# CH32V005F6U6.net
KiCad netlist of a schematic drawn in Altium Designer
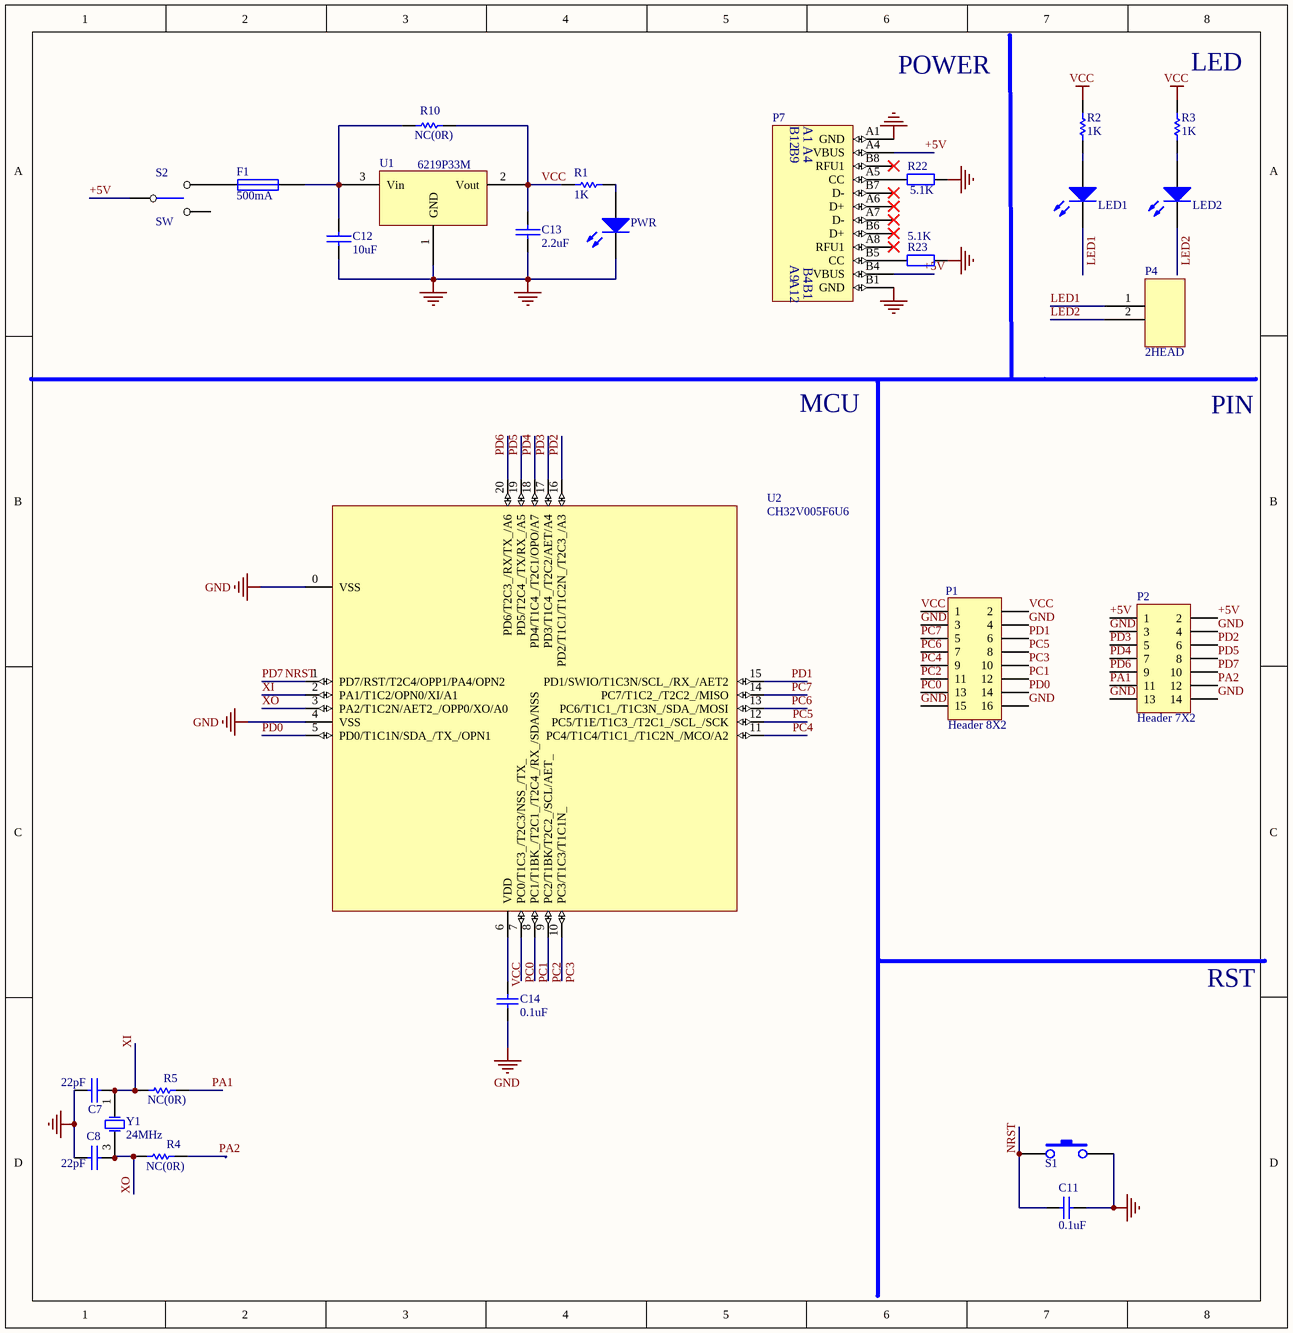
[diagram p0: CH32V005F6U6.SchDoc]

(export (version "E")
  (design (tool "Eeschema 10.0.6"))
  (components
    (comp (ref "C7")
      (value "22pF")
      (footprint "0402_C")
      (description "Capacitor")
      (libsource (lib "*") (part "CAP"))
    )
    (comp (ref "C8")
      (value "22pF")
      (footprint "0402_C")
      (description "Capacitor")
      (libsource (lib "*") (part "CAP"))
    )
    (comp (ref "C11")
      (value "0.1uF")
      (footprint "0603_C")
      (description "Capacitor")
      (fields (field (name "PUBLISHER") "Altium Limited"))
      (libsource (lib "*") (part "Cap"))
    )
    (comp (ref "C12")
      (value "10uF")
      (footprint "0603_C")
      (description "Capacitor")
      (libsource (lib "wch_sch_others") (part "CAP"))
    )
    (comp (ref "C13")
      (value "2.2uF")
      (footprint "0402_C")
      (description "Capacitor")
      (libsource (lib "wch_sch_others") (part "CAP"))
    )
    (comp (ref "C14")
      (value "0.1uF")
      (footprint "0603_C")
      (description "Capacitor")
      (fields (field (name "PUBLISHER") "Altium Limited"))
      (libsource (lib "*") (part "Cap"))
    )
    (comp (ref "F1")
      (value "500mA")
      (footprint "0603")
      (description "Fuse")
      (libsource (lib "*") (part "FUSE1"))
    )
    (comp (ref "LED1")
      (value "LED1   blue")
      (footprint "0603+")
      (description "Typical INFRARED GaAs LED")
      (fields (field (name "PUBLISHER") "Altium Limited"))
      (libsource (lib "") (part "LED0_1"))
    )
    (comp (ref "LED2")
      (value "LED2  blue")
      (footprint "0603+")
      (description "Typical INFRARED GaAs LED")
      (fields (field (name "PUBLISHER") "Altium Limited"))
      (libsource (lib "") (part "LED0_1"))
    )
    (comp (ref "P1")
      (value "Header 8X2")
      (footprint "HDR2X8")
      (description "Header, 8-Pin, Dual row")
      (fields (field (name "PUBLISHER") "Altium Limited"))
      (libsource (lib "Miscellaneous Connectors") (part "Header 8X2"))
    )
    (comp (ref "P2")
      (value "Header 7X2")
      (footprint "HDR2X7")
      (description "Header, 7-Pin, Dual row")
      (fields (field (name "PUBLISHER") "Altium Limited"))
      (libsource (lib "Miscellaneous Connectors") (part "Header 7X2"))
    )
    (comp (ref "P4") (value "2HEAD") (footprint "SIP2-2.54mm") (libsource (lib "*") (part "2HEAD")))
    (comp (ref "P7")
      (value "TYPE-C")
      (footprint "TYPE-C-Receptacle-2.0")
      (libsource (lib "*") (part "TYPE-C1"))
    )
    (comp (ref "PWR")
      (value "POWER  red")
      (footprint "0603+")
      (description "Typical INFRARED GaAs LED")
      (fields (field (name "PUBLISHER") "Altium Limited"))
      (libsource (lib "*") (part "LED0"))
    )
    (comp (ref "R1")
      (value "1K")
      (footprint "0402")
      (description "Semiconductor Resistor")
      (fields (field (name "PUBLISHER") "Altium Limited"))
      (libsource (lib "*") (part "Res Semi"))
    )
    (comp (ref "R2")
      (value "1K")
      (footprint "0402")
      (description "Semiconductor Resistor")
      (fields (field (name "PUBLISHER") "Altium Limited"))
      (libsource (lib "*") (part "Res Semi"))
    )
    (comp (ref "R3")
      (value "1K")
      (footprint "0402")
      (description "Semiconductor Resistor")
      (fields (field (name "PUBLISHER") "Altium Limited"))
      (libsource (lib "*") (part "Res Semi"))
    )
    (comp (ref "R4")
      (value "NC(0R)")
      (footprint "0402")
      (description "Semiconductor Resistor")
      (fields (field (name "Comment") "0R") (field (name "PUBLISHER") "Altium Limited"))
      (libsource (lib "*") (part "Res Semi"))
    )
    (comp (ref "R5")
      (value "NC(0R)")
      (footprint "0402")
      (description "Semiconductor Resistor")
      (fields (field (name "Comment") "0R") (field (name "PUBLISHER") "Altium Limited"))
      (libsource (lib "*") (part "Res Semi"))
    )
    (comp (ref "R10")
      (value "NC(0R)")
      (footprint "0402")
      (description "Semiconductor Resistor")
      (fields (field (name "Comment") "0R") (field (name "PUBLISHER") "Altium Limited"))
      (libsource (lib "*") (part "Res Semi"))
    )
    (comp (ref "R22")
      (value "5.1K")
      (footprint "0402")
      (description "Resistor")
      (libsource (lib "Miscellaneous Devices") (part "Res2"))
    )
    (comp (ref "R23")
      (value "5.1K")
      (footprint "0402")
      (description "Resistor")
      (libsource (lib "Miscellaneous Devices") (part "Res2"))
    )
    (comp (ref "S1") (value "NRST") (footprint "SMD_6.1x3.65x2.5mm-KEY") (libsource (lib "*") (part "KEY")))
    (comp (ref "S2") (value "SW") (footprint "SW1") (libsource (lib "*") (part "SW")))
    (comp (ref "U1")
      (value "6219P33M")
      (footprint "SOT-23")
      (libsource (lib "wch_sch_others") (part "6219P33M"))
    )
    (comp (ref "U2")
      (value "CH32V005F6U6")
      (footprint "QFN20_3X3")
      (description "RISC-V MCU, 48MHz, ADC/OPA/2*UART/I2C/SPI")
      (libsource (lib "DHXXXSCH") (part "CH32V005F6U6"))
    )
    (comp (ref "Y1")
      (value "24MHz")
      (footprint "XT3225")
      (description "Crystal Oscillator")
      (fields (field (name "PUBLISHER") "Altium Limited"))
      (libsource (lib "*") (part "XTAL"))
    )
  )
  (nets
    (net (code "1") (name "/+5V") (class "Default")
      (node (ref "P2") (pin "1") (pinfunction "1_1") (pintype "passive"))
      (node (ref "P2") (pin "2") (pinfunction "2_2") (pintype "passive"))
      (node (ref "P7") (pin "A4") (pinfunction "VBUS_A4") (pintype "bidirectional"))
      (node (ref "P7") (pin "B4") (pinfunction "VBUS_B4") (pintype "bidirectional"))
      (node (ref "S2") (pin "1") (pinfunction "1_1") (pintype "passive"))
    )
    (net (code "2") (name "/LED1") (class "Default")
      (node (ref "LED1") (pin "2") (pinfunction "K_2") (pintype "passive"))
      (node (ref "P4") (pin "1") (pintype "passive"))
    )
    (net (code "3") (name "/LED2") (class "Default")
      (node (ref "LED2") (pin "2") (pinfunction "K_2") (pintype "passive"))
      (node (ref "P4") (pin "2") (pintype "passive"))
    )
    (net (code "4") (name "/NRST") (class "Default")
      (node (ref "C11") (pin "2") (pinfunction "2_2") (pintype "passive"))
      (node (ref "P2") (pin "10") (pinfunction "10_10") (pintype "passive"))
      (node (ref "S1") (pin "1") (pinfunction "1_1") (pintype "passive"))
      (node (ref "U2") (pin "1") (pinfunction "PD7/RST/T2C4/OPP1/PA4/OPN2_1") (pintype "bidirectional"))
    )
    (net (code "5") (name "/PA1") (class "Default")
      (node (ref "P2") (pin "11") (pinfunction "11_11") (pintype "passive"))
      (node (ref "R5") (pin "2") (pinfunction "2_2") (pintype "passive"))
    )
    (net (code "6") (name "/PA2") (class "Default")
      (node (ref "P2") (pin "12") (pinfunction "12_12") (pintype "passive"))
      (node (ref "R4") (pin "2") (pinfunction "2_2") (pintype "passive"))
    )
    (net (code "7") (name "/PC0") (class "Default")
      (node (ref "P1") (pin "13") (pinfunction "13_13") (pintype "passive"))
      (node (ref "U2") (pin "7") (pinfunction "PC0/T1C3_/T2C3/NSS_/TX__7") (pintype "bidirectional"))
    )
    (net (code "8") (name "/PC1") (class "Default")
      (node (ref "P1") (pin "12") (pinfunction "12_12") (pintype "passive"))
      (node (ref "U2") (pin "8") (pinfunction "PC1/T1BK_/T2C1_/T2C4_/RX_/SDA/NSS_8") (pintype "bidirectional"))
    )
    (net (code "9") (name "/PC2") (class "Default")
      (node (ref "P1") (pin "11") (pinfunction "11_11") (pintype "passive"))
      (node (ref "U2") (pin "9") (pinfunction "PC2/T1BK/T2C2_/SCL/AET__9") (pintype "bidirectional"))
    )
    (net (code "10") (name "/PC3") (class "Default")
      (node (ref "P1") (pin "10") (pinfunction "10_10") (pintype "passive"))
      (node (ref "U2") (pin "10") (pinfunction "PC3/T1C3/T1C1N__10") (pintype "bidirectional"))
    )
    (net (code "11") (name "/PC4") (class "Default")
      (node (ref "P1") (pin "9") (pinfunction "9_9") (pintype "passive"))
      (node (ref "U2") (pin "11") (pinfunction "PC4/T1C4/T1C1_/T1C2N_/MCO/A2_11") (pintype "bidirectional"))
    )
    (net (code "12") (name "/PC5") (class "Default")
      (node (ref "P1") (pin "8") (pinfunction "8_8") (pintype "passive"))
      (node (ref "U2") (pin "12") (pinfunction "PC5/T1E/T1C3_/T2C1_/SCL_/SCK_12") (pintype "bidirectional"))
    )
    (net (code "13") (name "/PC6") (class "Default")
      (node (ref "P1") (pin "7") (pinfunction "7_7") (pintype "passive"))
      (node (ref "U2") (pin "13") (pinfunction "PC6/T1C1_/T1C3N_/SDA_/MOSI_13") (pintype "bidirectional"))
    )
    (net (code "14") (name "/PC7") (class "Default")
      (node (ref "P1") (pin "5") (pinfunction "5_5") (pintype "passive"))
      (node (ref "U2") (pin "14") (pinfunction "PC7/T1C2_/T2C2_/MISO_14") (pintype "bidirectional"))
    )
    (net (code "15") (name "/PD0") (class "Default")
      (node (ref "P1") (pin "14") (pinfunction "14_14") (pintype "passive"))
      (node (ref "U2") (pin "5") (pinfunction "PD0/T1C1N/SDA_/TX_/OPN1_5") (pintype "bidirectional"))
    )
    (net (code "16") (name "/PD1") (class "Default")
      (node (ref "P1") (pin "6") (pinfunction "6_6") (pintype "passive"))
      (node (ref "U2") (pin "15") (pinfunction "PD1/SWIO/T1C3N/SCL_/RX_/AET2_15") (pintype "bidirectional"))
    )
    (net (code "17") (name "/PD2") (class "Default")
      (node (ref "P2") (pin "6") (pinfunction "6_6") (pintype "passive"))
      (node (ref "U2") (pin "16") (pinfunction "PD2/T1C1/T1C2N_/T2C3_/A3_16") (pintype "bidirectional"))
    )
    (net (code "18") (name "/PD3") (class "Default")
      (node (ref "P2") (pin "5") (pinfunction "5_5") (pintype "passive"))
      (node (ref "U2") (pin "17") (pinfunction "PD3/T1C4_/T2C2/AET/A4_17") (pintype "bidirectional"))
    )
    (net (code "19") (name "/PD4") (class "Default")
      (node (ref "P2") (pin "7") (pinfunction "7_7") (pintype "passive"))
      (node (ref "U2") (pin "18") (pinfunction "PD4/T1C4_/T2C1/OPO/A7_18") (pintype "bidirectional"))
    )
    (net (code "20") (name "/PD5") (class "Default")
      (node (ref "P2") (pin "8") (pinfunction "8_8") (pintype "passive"))
      (node (ref "U2") (pin "19") (pinfunction "PD5/T2C4_/TX/RX_/A5_19") (pintype "bidirectional"))
    )
    (net (code "21") (name "/PD6") (class "Default")
      (node (ref "P2") (pin "9") (pinfunction "9_9") (pintype "passive"))
      (node (ref "U2") (pin "20") (pinfunction "PD6/T2C3_/RX/TX_/A6_20") (pintype "bidirectional"))
    )
    (net (code "22") (name "/XI") (class "Default")
      (node (ref "C7") (pin "2") (pinfunction "2_2") (pintype "passive"))
      (node (ref "R5") (pin "1") (pinfunction "1_1") (pintype "passive"))
      (node (ref "U2") (pin "2") (pinfunction "PA1/T1C2/OPN0/XI/A1_2") (pintype "bidirectional"))
      (node (ref "Y1") (pin "1") (pinfunction "OSC1_1") (pintype "passive"))
    )
    (net (code "23") (name "/XO") (class "Default")
      (node (ref "C8") (pin "2") (pinfunction "2_2") (pintype "passive"))
      (node (ref "R4") (pin "1") (pinfunction "1_1") (pintype "passive"))
      (node (ref "U2") (pin "3") (pinfunction "PA2/T1C2N/AET2_/OPP0/XO/A0_3") (pintype "bidirectional"))
      (node (ref "Y1") (pin "3") (pinfunction "OSC2_3") (pintype "passive"))
    )
    (net (code "24") (name "GND") (class "Default")
      (node (ref "C11") (pin "1") (pinfunction "1_1") (pintype "passive"))
      (node (ref "C12") (pin "2") (pinfunction "2_2") (pintype "passive"))
      (node (ref "C13") (pin "1") (pinfunction "1_1") (pintype "passive"))
      (node (ref "C14") (pin "2") (pinfunction "2_2") (pintype "passive"))
      (node (ref "C7") (pin "1") (pinfunction "1_1") (pintype "passive"))
      (node (ref "C8") (pin "1") (pinfunction "1_1") (pintype "passive"))
      (node (ref "P1") (pin "15") (pinfunction "15_15") (pintype "passive"))
      (node (ref "P1") (pin "16") (pinfunction "16_16") (pintype "passive"))
      (node (ref "P1") (pin "3") (pinfunction "3_3") (pintype "passive"))
      (node (ref "P1") (pin "4") (pinfunction "4_4") (pintype "passive"))
      (node (ref "P2") (pin "13") (pinfunction "13_13") (pintype "passive"))
      (node (ref "P2") (pin "14") (pinfunction "14_14") (pintype "passive"))
      (node (ref "P2") (pin "3") (pinfunction "3_3") (pintype "passive"))
      (node (ref "P2") (pin "4") (pinfunction "4_4") (pintype "passive"))
      (node (ref "P7") (pin "A1") (pinfunction "GND_A1") (pintype "bidirectional"))
      (node (ref "P7") (pin "B1") (pinfunction "GND_B1") (pintype "bidirectional"))
      (node (ref "PWR") (pin "2") (pinfunction "K_2") (pintype "passive"))
      (node (ref "R22") (pin "2") (pinfunction "2_2") (pintype "passive"))
      (node (ref "R23") (pin "2") (pinfunction "2_2") (pintype "passive"))
      (node (ref "S1") (pin "2") (pinfunction "2_2") (pintype "passive"))
      (node (ref "U1") (pin "1") (pinfunction "GND_1") (pintype "passive"))
      (node (ref "U2") (pin "0") (pinfunction "VSS_0") (pintype "power_in"))
      (node (ref "U2") (pin "4") (pinfunction "VSS_4") (pintype "power_in"))
    )
    (net (code "25") (name "Net-(F1-Pad1)") (class "Default")
      (node (ref "F1") (pin "1") (pinfunction "1_1") (pintype "passive"))
      (node (ref "S2") (pin "3") (pinfunction "3_3") (pintype "passive"))
    )
    (net (code "26") (name "Net-(LED1-A)") (class "Default")
      (node (ref "LED1") (pin "1") (pinfunction "A_1") (pintype "passive"))
      (node (ref "R2") (pin "2") (pinfunction "2_2") (pintype "passive"))
    )
    (net (code "27") (name "Net-(LED2-A)") (class "Default")
      (node (ref "LED2") (pin "1") (pinfunction "A_1") (pintype "passive"))
      (node (ref "R3") (pin "2") (pinfunction "2_2") (pintype "passive"))
    )
    (net (code "28") (name "Net-(P7-CC-PadA5)") (class "Default")
      (node (ref "P7") (pin "A5") (pinfunction "CC_A5") (pintype "bidirectional"))
      (node (ref "R22") (pin "1") (pinfunction "1_1") (pintype "passive"))
    )
    (net (code "29") (name "Net-(P7-CC-PadB5)") (class "Default")
      (node (ref "P7") (pin "B5") (pinfunction "CC_B5") (pintype "bidirectional"))
      (node (ref "R23") (pin "1") (pinfunction "1_1") (pintype "passive"))
    )
    (net (code "30") (name "Net-(PWR-A)") (class "Default")
      (node (ref "PWR") (pin "1") (pinfunction "A_1") (pintype "passive"))
      (node (ref "R1") (pin "1") (pinfunction "1_1") (pintype "passive"))
    )
    (net (code "31") (name "Net-(U1-Vin)") (class "Default")
      (node (ref "C12") (pin "1") (pinfunction "1_1") (pintype "passive"))
      (node (ref "F1") (pin "2") (pinfunction "2_2") (pintype "passive"))
      (node (ref "R10") (pin "1") (pinfunction "1_1") (pintype "passive"))
      (node (ref "U1") (pin "3") (pinfunction "Vin_3") (pintype "passive"))
    )
    (net (code "32") (name "VCC") (class "Default")
      (node (ref "C13") (pin "2") (pinfunction "2_2") (pintype "passive"))
      (node (ref "C14") (pin "1") (pinfunction "1_1") (pintype "passive"))
      (node (ref "P1") (pin "1") (pinfunction "1_1") (pintype "passive"))
      (node (ref "P1") (pin "2") (pinfunction "2_2") (pintype "passive"))
      (node (ref "R1") (pin "2") (pinfunction "2_2") (pintype "passive"))
      (node (ref "R10") (pin "2") (pinfunction "2_2") (pintype "passive"))
      (node (ref "R2") (pin "1") (pinfunction "1_1") (pintype "passive"))
      (node (ref "R3") (pin "1") (pinfunction "1_1") (pintype "passive"))
      (node (ref "U1") (pin "2") (pinfunction "Vout_2") (pintype "passive"))
      (node (ref "U2") (pin "6") (pinfunction "VDD_6") (pintype "power_in"))
    )
    (net (code "33") (name "unconnected-(P7-D+-PadA6)") (class "Default")
      (node (ref "P7") (pin "A6") (pinfunction "D+_A6") (pintype "bidirectional+no_connect"))
    )
    (net (code "34") (name "unconnected-(P7-D+-PadB6)") (class "Default")
      (node (ref "P7") (pin "B6") (pinfunction "D+_B6") (pintype "bidirectional+no_connect"))
    )
    (net (code "35") (name "unconnected-(P7-D--PadA7)") (class "Default")
      (node (ref "P7") (pin "A7") (pinfunction "D-_A7") (pintype "bidirectional+no_connect"))
    )
    (net (code "36") (name "unconnected-(P7-D--PadB7)") (class "Default")
      (node (ref "P7") (pin "B7") (pinfunction "D-_B7") (pintype "bidirectional+no_connect"))
    )
    (net (code "37") (name "unconnected-(P7-RFU1-PadA8)") (class "Default")
      (node (ref "P7") (pin "A8") (pinfunction "RFU1_A8") (pintype "bidirectional+no_connect"))
    )
    (net (code "38") (name "unconnected-(P7-RFU1-PadB8)") (class "Default")
      (node (ref "P7") (pin "B8") (pinfunction "RFU1_B8") (pintype "bidirectional+no_connect"))
    )
    (net (code "39") (name "unconnected-(S2-Pad2)") (class "Default")
      (node (ref "S2") (pin "2") (pinfunction "2_2") (pintype "passive"))
    )
  )
)
